# toplevel.net
KiCad netlist of a schematic drawn in Altium Designer
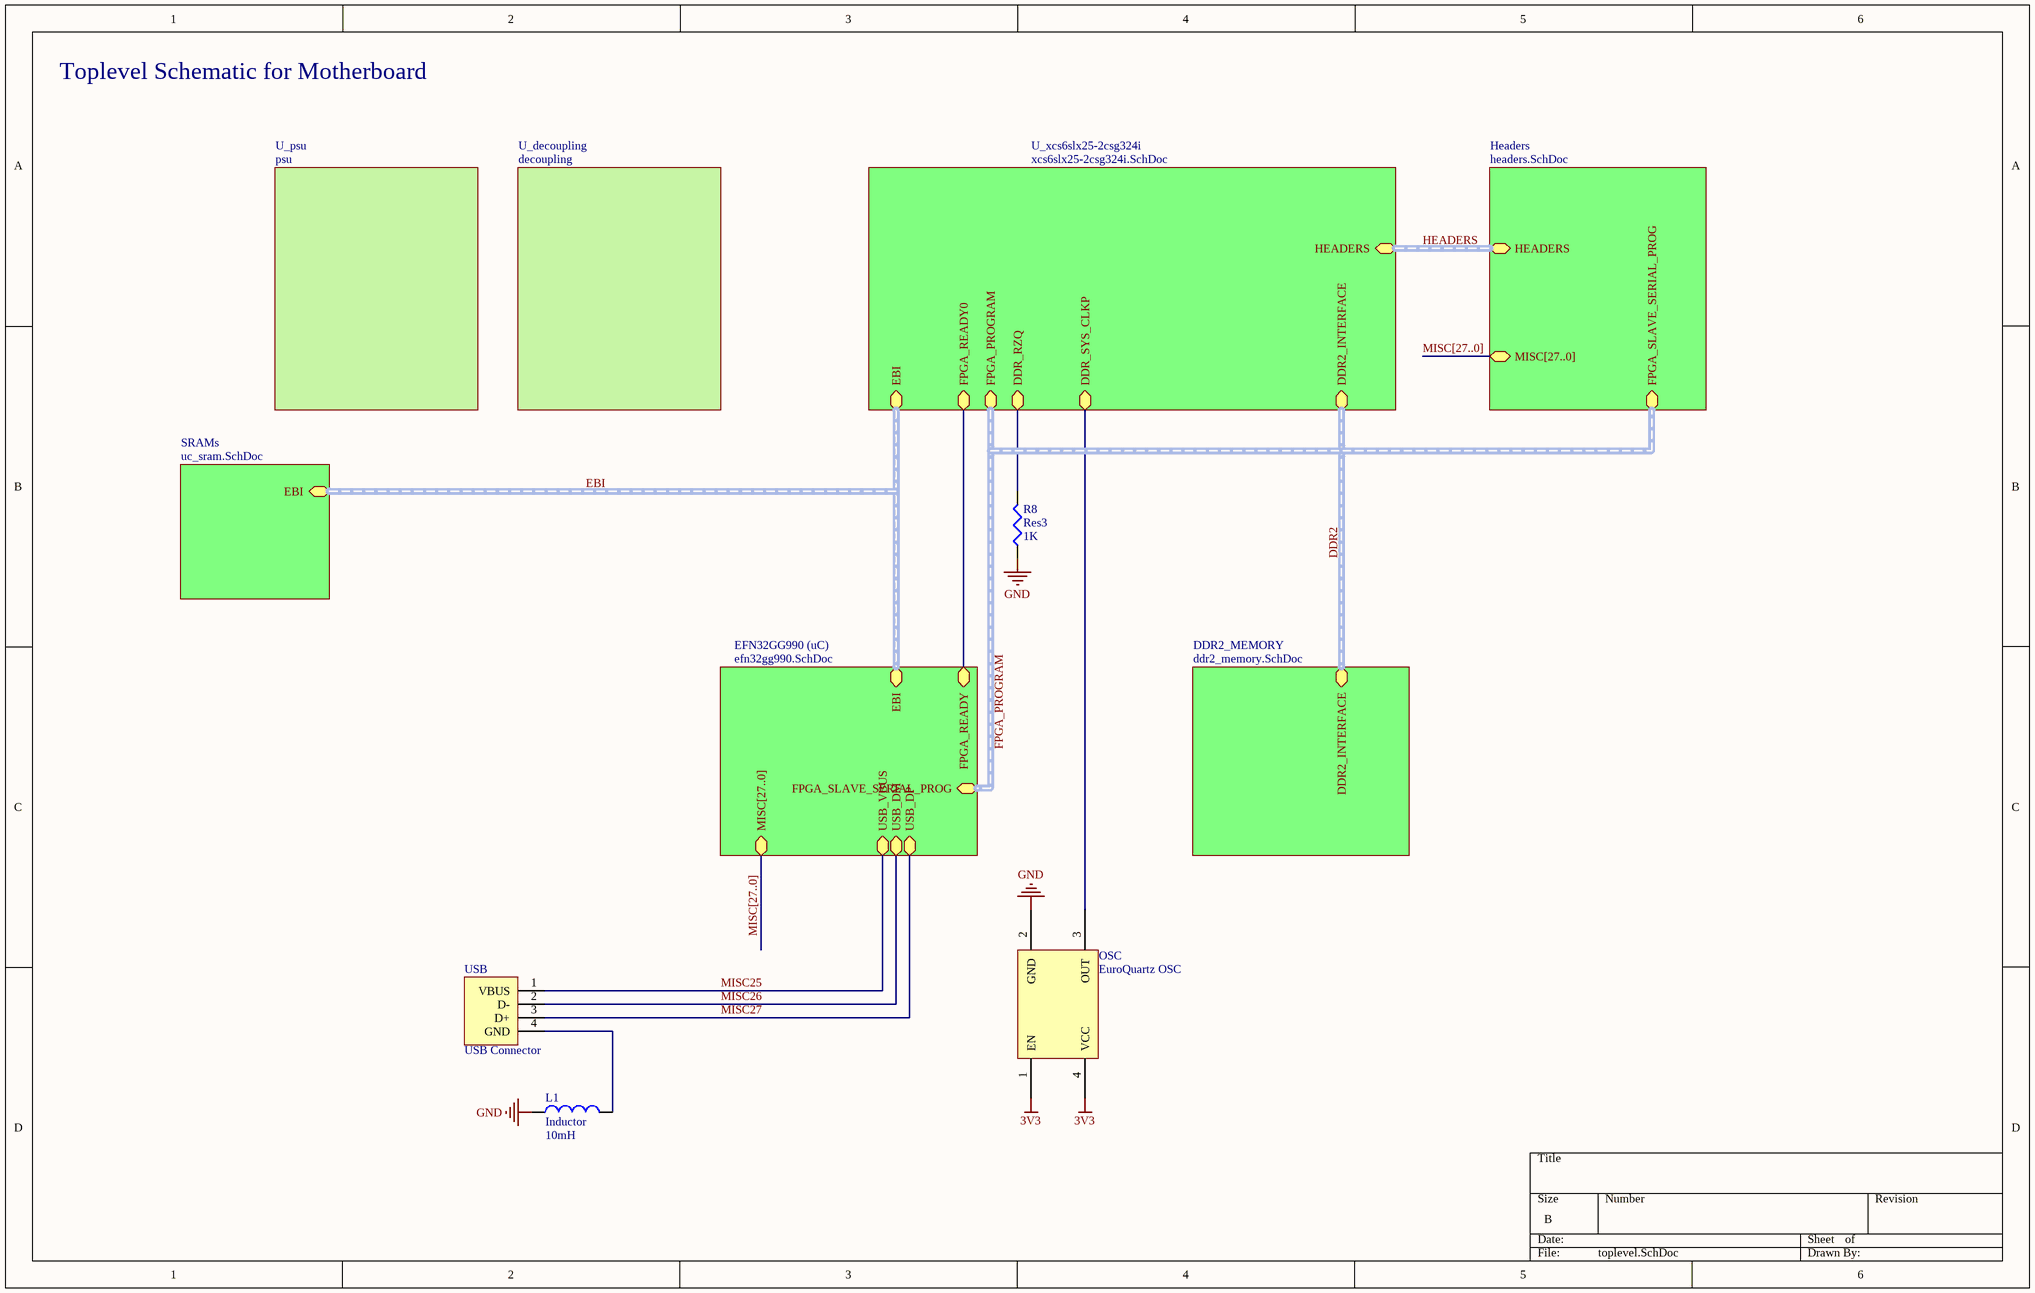
[diagram p0: toplevel.SchDoc]

(export (version "E")
  (design (tool "Eeschema 10.0.6"))
  (components
    (comp (ref "L1")
      (value "Inductor")
      (footprint "C1210")
      (fields (field (name "ALTIUM_VALUE") "10mH") (field (name "PUBLISHER") "Altium Limited"))
      (libsource (lib "Miscellaneous Devices") (part "Inductor"))
    )
    (comp (ref "OSC")
      (value "EuroQuartz OSC")
      (footprint "SOP4")
      (description "XO53050UITA")
      (libsource (lib "ORLY_Lib") (part "EuroQuartz OSC"))
    )
    (comp (ref "R8")
      (value "Res3")
      (footprint "14-1210")
      (description "Resistor")
      (fields (field (name "ALTIUM_VALUE") "1K") (field (name "PUBLISHER") "Altium Limited"))
      (libsource (lib "Miscellaneous Devices") (part "Res3"))
    )
    (comp (ref "USB")
      (value "USB Connector")
      (footprint "USB2.5-2H4D")
      (libsource (lib "ORLY_Lib") (part "USB Connector"))
    )
  )
  (nets
    (net (code "30") (name "/DDR_RZQ") (class "Default")
      (node (ref "R8") (pin "2") (pinfunction "2_2") (pintype "passive"))
    )
    (net (code "31") (name "/DDR_SYS_CLKP") (class "Default")
      (node (ref "OSC") (pin "3") (pinfunction "OUT_3") (pintype "passive"))
    )
    (net (code "35") (name "/MISC25") (class "Default")
      (node (ref "USB") (pin "1") (pinfunction "VBUS_1") (pintype "passive"))
    )
    (net (code "36") (name "/MISC26") (class "Default")
      (node (ref "USB") (pin "2") (pinfunction "D-_2") (pintype "passive"))
    )
    (net (code "37") (name "/MISC27") (class "Default")
      (node (ref "USB") (pin "3") (pinfunction "D+_3") (pintype "passive"))
    )
    (net (code "43") (name "3V3") (class "Default")
      (node (ref "OSC") (pin "1") (pinfunction "EN_1") (pintype "passive"))
      (node (ref "OSC") (pin "4") (pinfunction "VCC_4") (pintype "passive"))
    )
    (net (code "44") (name "GND") (class "Default")
      (node (ref "L1") (pin "1") (pinfunction "1_1") (pintype "passive"))
      (node (ref "OSC") (pin "2") (pinfunction "GND_2") (pintype "passive"))
      (node (ref "R8") (pin "1") (pinfunction "1_1") (pintype "passive"))
    )
    (net (code "45") (name "Net-(USB-GND)") (class "Default")
      (node (ref "L1") (pin "2") (pinfunction "2_2") (pintype "passive"))
      (node (ref "USB") (pin "4") (pinfunction "GND_4") (pintype "passive"))
    )
  )
)
